# TECBoard.net
KiCad netlist of a schematic drawn in Altium Designer
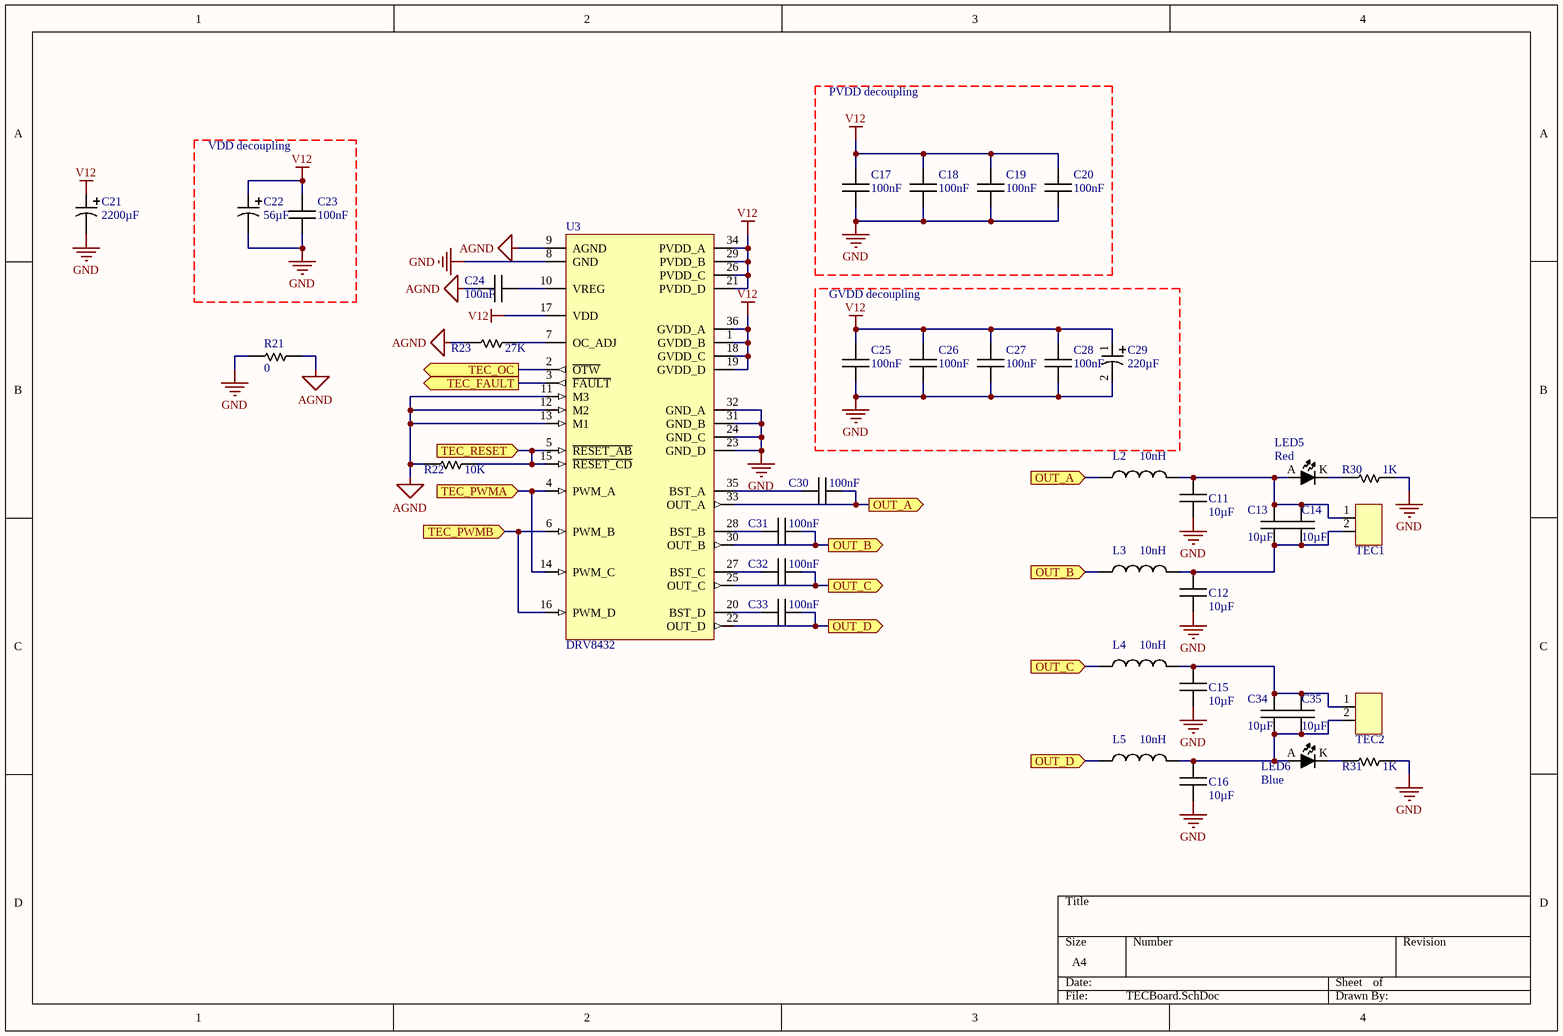
[diagram p0: TECBoard.SchDoc]

(export (version "E")
  (design (tool "Eeschema 10.0.6"))
  (components
    (comp (ref "C11") (value "10µF") (footprint "CAPC3225N") (libsource (lib "Megaxone") (part "Capacitor")))
    (comp (ref "C12") (value "10µF") (footprint "CAPC3225N") (libsource (lib "Megaxone") (part "Capacitor")))
    (comp (ref "C13") (value "10µF") (footprint "CAPC3225N") (libsource (lib "Megaxone") (part "Capacitor")))
    (comp (ref "C14") (value "10µF") (footprint "CAPC3225N") (libsource (lib "Megaxone") (part "Capacitor")))
    (comp (ref "C15") (value "10µF") (footprint "CAPC3225N") (libsource (lib "Megaxone") (part "Capacitor")))
    (comp (ref "C16") (value "10µF") (footprint "CAPC3225N") (libsource (lib "Megaxone") (part "Capacitor")))
    (comp (ref "C17") (value "100nF") (footprint "CAPC1608N") (libsource (lib "Megaxone") (part "Capacitor")))
    (comp (ref "C18") (value "100nF") (footprint "CAPC1608N") (libsource (lib "Megaxone") (part "Capacitor")))
    (comp (ref "C19") (value "100nF") (footprint "CAPC1608N") (libsource (lib "Megaxone") (part "Capacitor")))
    (comp (ref "C20") (value "100nF") (footprint "CAPC1608N") (libsource (lib "Megaxone") (part "Capacitor")))
    (comp (ref "C21")
      (value "2200µF")
      (footprint "CAPPR7.5-18x35.5")
      (libsource (lib "Megaxone") (part "Capacitor Polarised"))
    )
    (comp (ref "C22")
      (value "56µF")
      (footprint "CAPPR2.5-6.3x15")
      (libsource (lib "Megaxone") (part "Capacitor Polarised"))
    )
    (comp (ref "C23") (value "100nF") (footprint "CAPC1608N") (libsource (lib "Megaxone") (part "Capacitor")))
    (comp (ref "C24") (value "100nF") (footprint "CAPC1608N") (libsource (lib "Megaxone") (part "Capacitor")))
    (comp (ref "C25") (value "100nF") (footprint "CAPC1608N") (libsource (lib "Megaxone") (part "Capacitor")))
    (comp (ref "C26") (value "100nF") (footprint "CAPC1608N") (libsource (lib "Megaxone") (part "Capacitor")))
    (comp (ref "C27") (value "100nF") (footprint "CAPC1608N") (libsource (lib "Megaxone") (part "Capacitor")))
    (comp (ref "C28") (value "100nF") (footprint "CAPC1608N") (libsource (lib "Megaxone") (part "Capacitor")))
    (comp (ref "C29")
      (value "220µF")
      (footprint "CAPPR3.5-8x15")
      (libsource (lib "") (part "Capacitor Polarised_1"))
    )
    (comp (ref "C30") (value "100nF") (footprint "CAPC1608N") (libsource (lib "Megaxone") (part "Capacitor")))
    (comp (ref "C31") (value "100nF") (footprint "CAPC1608N") (libsource (lib "Megaxone") (part "Capacitor")))
    (comp (ref "C32") (value "100nF") (footprint "CAPC1608N") (libsource (lib "Megaxone") (part "Capacitor")))
    (comp (ref "C33") (value "100nF") (footprint "CAPC1608N") (libsource (lib "Megaxone") (part "Capacitor")))
    (comp (ref "C34") (value "10µF") (footprint "CAPC3225N") (libsource (lib "Megaxone") (part "Capacitor")))
    (comp (ref "C35") (value "10µF") (footprint "CAPC3225N") (libsource (lib "Megaxone") (part "Capacitor")))
    (comp (ref "L2")
      (value "10nH")
      (footprint "Inductor 9.1×7.6mm TH")
      (libsource (lib "Megaxone") (part "Inductor"))
    )
    (comp (ref "L3")
      (value "10nH")
      (footprint "Inductor 9.1×7.6mm TH")
      (libsource (lib "Megaxone") (part "Inductor"))
    )
    (comp (ref "L4")
      (value "10nH")
      (footprint "Inductor 9.1×7.6mm TH")
      (libsource (lib "Megaxone") (part "Inductor"))
    )
    (comp (ref "L5")
      (value "10nH")
      (footprint "Inductor 9.1×7.6mm TH")
      (libsource (lib "Megaxone") (part "Inductor"))
    )
    (comp (ref "LED5") (value "Red") (footprint "LED 1608m") (libsource (lib "Megaxone") (part "LED")))
    (comp (ref "LED6") (value "Blue") (footprint "LED 1608m") (libsource (lib "Megaxone") (part "LED")))
    (comp (ref "R21") (value "0") (footprint "RESC1608N") (libsource (lib "Megaxone") (part "Resistor")))
    (comp (ref "R22") (value "10K") (footprint "RESC1608N") (libsource (lib "Megaxone") (part "Resistor")))
    (comp (ref "R23") (value "27K") (footprint "RESC2012N") (libsource (lib "Megaxone") (part "Resistor")))
    (comp (ref "R30") (value "1K") (footprint "RESC1608N") (libsource (lib "Megaxone") (part "Resistor")))
    (comp (ref "R31") (value "1K") (footprint "RESC1608N") (libsource (lib "Megaxone") (part "Resistor")))
    (comp (ref "TEC1")
      (value "High-Power Connector 2p")
      (footprint "High-Power Connector 2")
      (libsource (lib "Megaxone") (part "High-Power Connector 2p"))
    )
    (comp (ref "TEC2")
      (value "High-Power Connector 2p")
      (footprint "High-Power Connector 2")
      (libsource (lib "Megaxone") (part "High-Power Connector 2p"))
    )
    (comp (ref "U3") (value "DRV8432") (footprint "PSOP3-36") (libsource (lib "Megaxone") (part "DRV8432")))
  )
  (nets
    (net (code "1") (name "/OUT_A") (class "Default")
      (node (ref "C30") (pin "2") (pinfunction "2_2") (pintype "passive"))
      (node (ref "L2") (pin "1") (pinfunction "1_1") (pintype "passive"))
      (node (ref "U3") (pin "33") (pinfunction "OUT_A_33") (pintype "output"))
    )
    (net (code "2") (name "/OUT_B") (class "Default")
      (node (ref "C31") (pin "2") (pinfunction "2_2") (pintype "passive"))
      (node (ref "L3") (pin "1") (pinfunction "1_1") (pintype "passive"))
      (node (ref "U3") (pin "30") (pinfunction "OUT_B_30") (pintype "output"))
    )
    (net (code "3") (name "/OUT_C") (class "Default")
      (node (ref "C32") (pin "2") (pinfunction "2_2") (pintype "passive"))
      (node (ref "L4") (pin "1") (pinfunction "1_1") (pintype "passive"))
      (node (ref "U3") (pin "25") (pinfunction "OUT_C_25") (pintype "output"))
    )
    (net (code "4") (name "/OUT_D") (class "Default")
      (node (ref "C33") (pin "2") (pinfunction "2_2") (pintype "passive"))
      (node (ref "L5") (pin "1") (pinfunction "1_1") (pintype "passive"))
      (node (ref "U3") (pin "22") (pinfunction "OUT_D_22") (pintype "output"))
    )
    (net (code "5") (name "/TEC_FAULT") (class "Default")
      (node (ref "U3") (pin "3") (pinfunction "~{FAULT}_3") (pintype "output"))
    )
    (net (code "6") (name "/TEC_OC") (class "Default")
      (node (ref "U3") (pin "2") (pinfunction "~{OTW}_2") (pintype "output"))
    )
    (net (code "7") (name "/TEC_PWMA") (class "Default")
      (node (ref "U3") (pin "14") (pinfunction "PWM_C_14") (pintype "input"))
      (node (ref "U3") (pin "4") (pinfunction "PWM_A_4") (pintype "input"))
    )
    (net (code "8") (name "/TEC_PWMB") (class "Default")
      (node (ref "U3") (pin "16") (pinfunction "PWM_D_16") (pintype "input"))
      (node (ref "U3") (pin "6") (pinfunction "PWM_B_6") (pintype "input"))
    )
    (net (code "9") (name "/TEC_RESET") (class "Default")
      (node (ref "R22") (pin "2") (pinfunction "2_2") (pintype "passive"))
      (node (ref "U3") (pin "15") (pinfunction "~{RESET_CD}_15") (pintype "input"))
      (node (ref "U3") (pin "5") (pinfunction "~{RESET_AB}_5") (pintype "input"))
    )
    (net (code "10") (name "AGND") (class "Default")
      (node (ref "C24") (pin "2") (pinfunction "2_2") (pintype "passive"))
      (node (ref "R21") (pin "2") (pinfunction "2_2") (pintype "passive"))
      (node (ref "R22") (pin "1") (pinfunction "1_1") (pintype "passive"))
      (node (ref "R23") (pin "1") (pinfunction "1_1") (pintype "passive"))
      (node (ref "U3") (pin "11") (pinfunction "M3_11") (pintype "input"))
      (node (ref "U3") (pin "12") (pinfunction "M2_12") (pintype "input"))
      (node (ref "U3") (pin "13") (pinfunction "M1_13") (pintype "input"))
      (node (ref "U3") (pin "9") (pinfunction "AGND_9") (pintype "power_in"))
    )
    (net (code "11") (name "GND") (class "Default")
      (node (ref "C11") (pin "1") (pinfunction "1_1") (pintype "passive"))
      (node (ref "C12") (pin "1") (pinfunction "1_1") (pintype "passive"))
      (node (ref "C15") (pin "1") (pinfunction "1_1") (pintype "passive"))
      (node (ref "C16") (pin "1") (pinfunction "1_1") (pintype "passive"))
      (node (ref "C17") (pin "1") (pinfunction "1_1") (pintype "passive"))
      (node (ref "C18") (pin "1") (pinfunction "1_1") (pintype "passive"))
      (node (ref "C19") (pin "1") (pinfunction "1_1") (pintype "passive"))
      (node (ref "C20") (pin "1") (pinfunction "1_1") (pintype "passive"))
      (node (ref "C21") (pin "2") (pinfunction "2_2") (pintype "passive"))
      (node (ref "C22") (pin "2") (pinfunction "2_2") (pintype "passive"))
      (node (ref "C23") (pin "1") (pinfunction "1_1") (pintype "passive"))
      (node (ref "C25") (pin "1") (pinfunction "1_1") (pintype "passive"))
      (node (ref "C26") (pin "1") (pinfunction "1_1") (pintype "passive"))
      (node (ref "C27") (pin "1") (pinfunction "1_1") (pintype "passive"))
      (node (ref "C28") (pin "1") (pinfunction "1_1") (pintype "passive"))
      (node (ref "C29") (pin "2") (pinfunction "2_2") (pintype "passive"))
      (node (ref "R21") (pin "1") (pinfunction "1_1") (pintype "passive"))
      (node (ref "R30") (pin "2") (pinfunction "2_2") (pintype "passive"))
      (node (ref "R31") (pin "2") (pinfunction "2_2") (pintype "passive"))
      (node (ref "U3") (pin "23") (pinfunction "GND_D_23") (pintype "power_in"))
      (node (ref "U3") (pin "24") (pinfunction "GND_C_24") (pintype "power_in"))
      (node (ref "U3") (pin "31") (pinfunction "GND_B_31") (pintype "power_in"))
      (node (ref "U3") (pin "32") (pinfunction "GND_A_32") (pintype "power_in"))
      (node (ref "U3") (pin "8") (pinfunction "GND_8") (pintype "power_in"))
    )
    (net (code "12") (name "Net-(C11-Pad2)") (class "Default")
      (node (ref "C11") (pin "2") (pinfunction "2_2") (pintype "passive"))
      (node (ref "C13") (pin "2") (pinfunction "2_2") (pintype "passive"))
      (node (ref "C14") (pin "2") (pinfunction "2_2") (pintype "passive"))
      (node (ref "L2") (pin "2") (pinfunction "2_2") (pintype "passive"))
      (node (ref "LED5") (pin "A") (pinfunction "A_A") (pintype "passive"))
      (node (ref "TEC1") (pin "1") (pinfunction "1_1") (pintype "power_in"))
    )
    (net (code "13") (name "Net-(C12-Pad2)") (class "Default")
      (node (ref "C12") (pin "2") (pinfunction "2_2") (pintype "passive"))
      (node (ref "C13") (pin "1") (pinfunction "1_1") (pintype "passive"))
      (node (ref "C14") (pin "1") (pinfunction "1_1") (pintype "passive"))
      (node (ref "L3") (pin "2") (pinfunction "2_2") (pintype "passive"))
      (node (ref "TEC1") (pin "2") (pinfunction "2_2") (pintype "power_in"))
    )
    (net (code "14") (name "Net-(C15-Pad2)") (class "Default")
      (node (ref "C15") (pin "2") (pinfunction "2_2") (pintype "passive"))
      (node (ref "C34") (pin "2") (pinfunction "2_2") (pintype "passive"))
      (node (ref "C35") (pin "2") (pinfunction "2_2") (pintype "passive"))
      (node (ref "L4") (pin "2") (pinfunction "2_2") (pintype "passive"))
      (node (ref "TEC2") (pin "1") (pinfunction "1_1") (pintype "power_in"))
    )
    (net (code "15") (name "Net-(C16-Pad2)") (class "Default")
      (node (ref "C16") (pin "2") (pinfunction "2_2") (pintype "passive"))
      (node (ref "C34") (pin "1") (pinfunction "1_1") (pintype "passive"))
      (node (ref "C35") (pin "1") (pinfunction "1_1") (pintype "passive"))
      (node (ref "L5") (pin "2") (pinfunction "2_2") (pintype "passive"))
      (node (ref "LED6") (pin "A") (pinfunction "A_A") (pintype "passive"))
      (node (ref "TEC2") (pin "2") (pinfunction "2_2") (pintype "power_in"))
    )
    (net (code "16") (name "Net-(LED5-PadK)") (class "Default")
      (node (ref "LED5") (pin "K") (pinfunction "K_K") (pintype "passive"))
      (node (ref "R30") (pin "1") (pinfunction "1_1") (pintype "passive"))
    )
    (net (code "17") (name "Net-(LED6-PadK)") (class "Default")
      (node (ref "LED6") (pin "K") (pinfunction "K_K") (pintype "passive"))
      (node (ref "R31") (pin "1") (pinfunction "1_1") (pintype "passive"))
    )
    (net (code "18") (name "Net-(U3-BST_A)") (class "Default")
      (node (ref "C30") (pin "1") (pinfunction "1_1") (pintype "passive"))
      (node (ref "U3") (pin "35") (pinfunction "BST_A_35") (pintype "passive"))
    )
    (net (code "19") (name "Net-(U3-BST_B)") (class "Default")
      (node (ref "C31") (pin "1") (pinfunction "1_1") (pintype "passive"))
      (node (ref "U3") (pin "28") (pinfunction "BST_B_28") (pintype "passive"))
    )
    (net (code "20") (name "Net-(U3-BST_C)") (class "Default")
      (node (ref "C32") (pin "1") (pinfunction "1_1") (pintype "passive"))
      (node (ref "U3") (pin "27") (pinfunction "BST_C_27") (pintype "passive"))
    )
    (net (code "21") (name "Net-(U3-BST_D)") (class "Default")
      (node (ref "C33") (pin "1") (pinfunction "1_1") (pintype "passive"))
      (node (ref "U3") (pin "20") (pinfunction "BST_D_20") (pintype "passive"))
    )
    (net (code "22") (name "Net-(U3-OC_ADJ)") (class "Default")
      (node (ref "R23") (pin "2") (pinfunction "2_2") (pintype "passive"))
      (node (ref "U3") (pin "7") (pinfunction "OC_ADJ_7") (pintype "passive"))
    )
    (net (code "23") (name "Net-(U3-VREG)") (class "Default")
      (node (ref "C24") (pin "1") (pinfunction "1_1") (pintype "passive"))
      (node (ref "U3") (pin "10") (pinfunction "VREG_10") (pintype "power_in"))
    )
    (net (code "24") (name "V12") (class "Default")
      (node (ref "C17") (pin "2") (pinfunction "2_2") (pintype "passive"))
      (node (ref "C18") (pin "2") (pinfunction "2_2") (pintype "passive"))
      (node (ref "C19") (pin "2") (pinfunction "2_2") (pintype "passive"))
      (node (ref "C20") (pin "2") (pinfunction "2_2") (pintype "passive"))
      (node (ref "C21") (pin "1") (pinfunction "1_1") (pintype "passive"))
      (node (ref "C22") (pin "1") (pinfunction "1_1") (pintype "passive"))
      (node (ref "C23") (pin "2") (pinfunction "2_2") (pintype "passive"))
      (node (ref "C25") (pin "2") (pinfunction "2_2") (pintype "passive"))
      (node (ref "C26") (pin "2") (pinfunction "2_2") (pintype "passive"))
      (node (ref "C27") (pin "2") (pinfunction "2_2") (pintype "passive"))
      (node (ref "C28") (pin "2") (pinfunction "2_2") (pintype "passive"))
      (node (ref "C29") (pin "1") (pinfunction "1_1") (pintype "passive"))
      (node (ref "U3") (pin "1") (pinfunction "GVDD_B_1") (pintype "power_in"))
      (node (ref "U3") (pin "17") (pinfunction "VDD_17") (pintype "power_in"))
      (node (ref "U3") (pin "18") (pinfunction "GVDD_C_18") (pintype "power_in"))
      (node (ref "U3") (pin "19") (pinfunction "GVDD_D_19") (pintype "power_in"))
      (node (ref "U3") (pin "21") (pinfunction "PVDD_D_21") (pintype "power_in"))
      (node (ref "U3") (pin "26") (pinfunction "PVDD_C_26") (pintype "power_in"))
      (node (ref "U3") (pin "29") (pinfunction "PVDD_B_29") (pintype "power_in"))
      (node (ref "U3") (pin "34") (pinfunction "PVDD_A_34") (pintype "power_in"))
      (node (ref "U3") (pin "36") (pinfunction "GVDD_A_36") (pintype "power_in"))
    )
  )
)
